# SH5_-_ARM_CONTROLS.net
KiCad netlist of a schematic drawn in Altium Designer
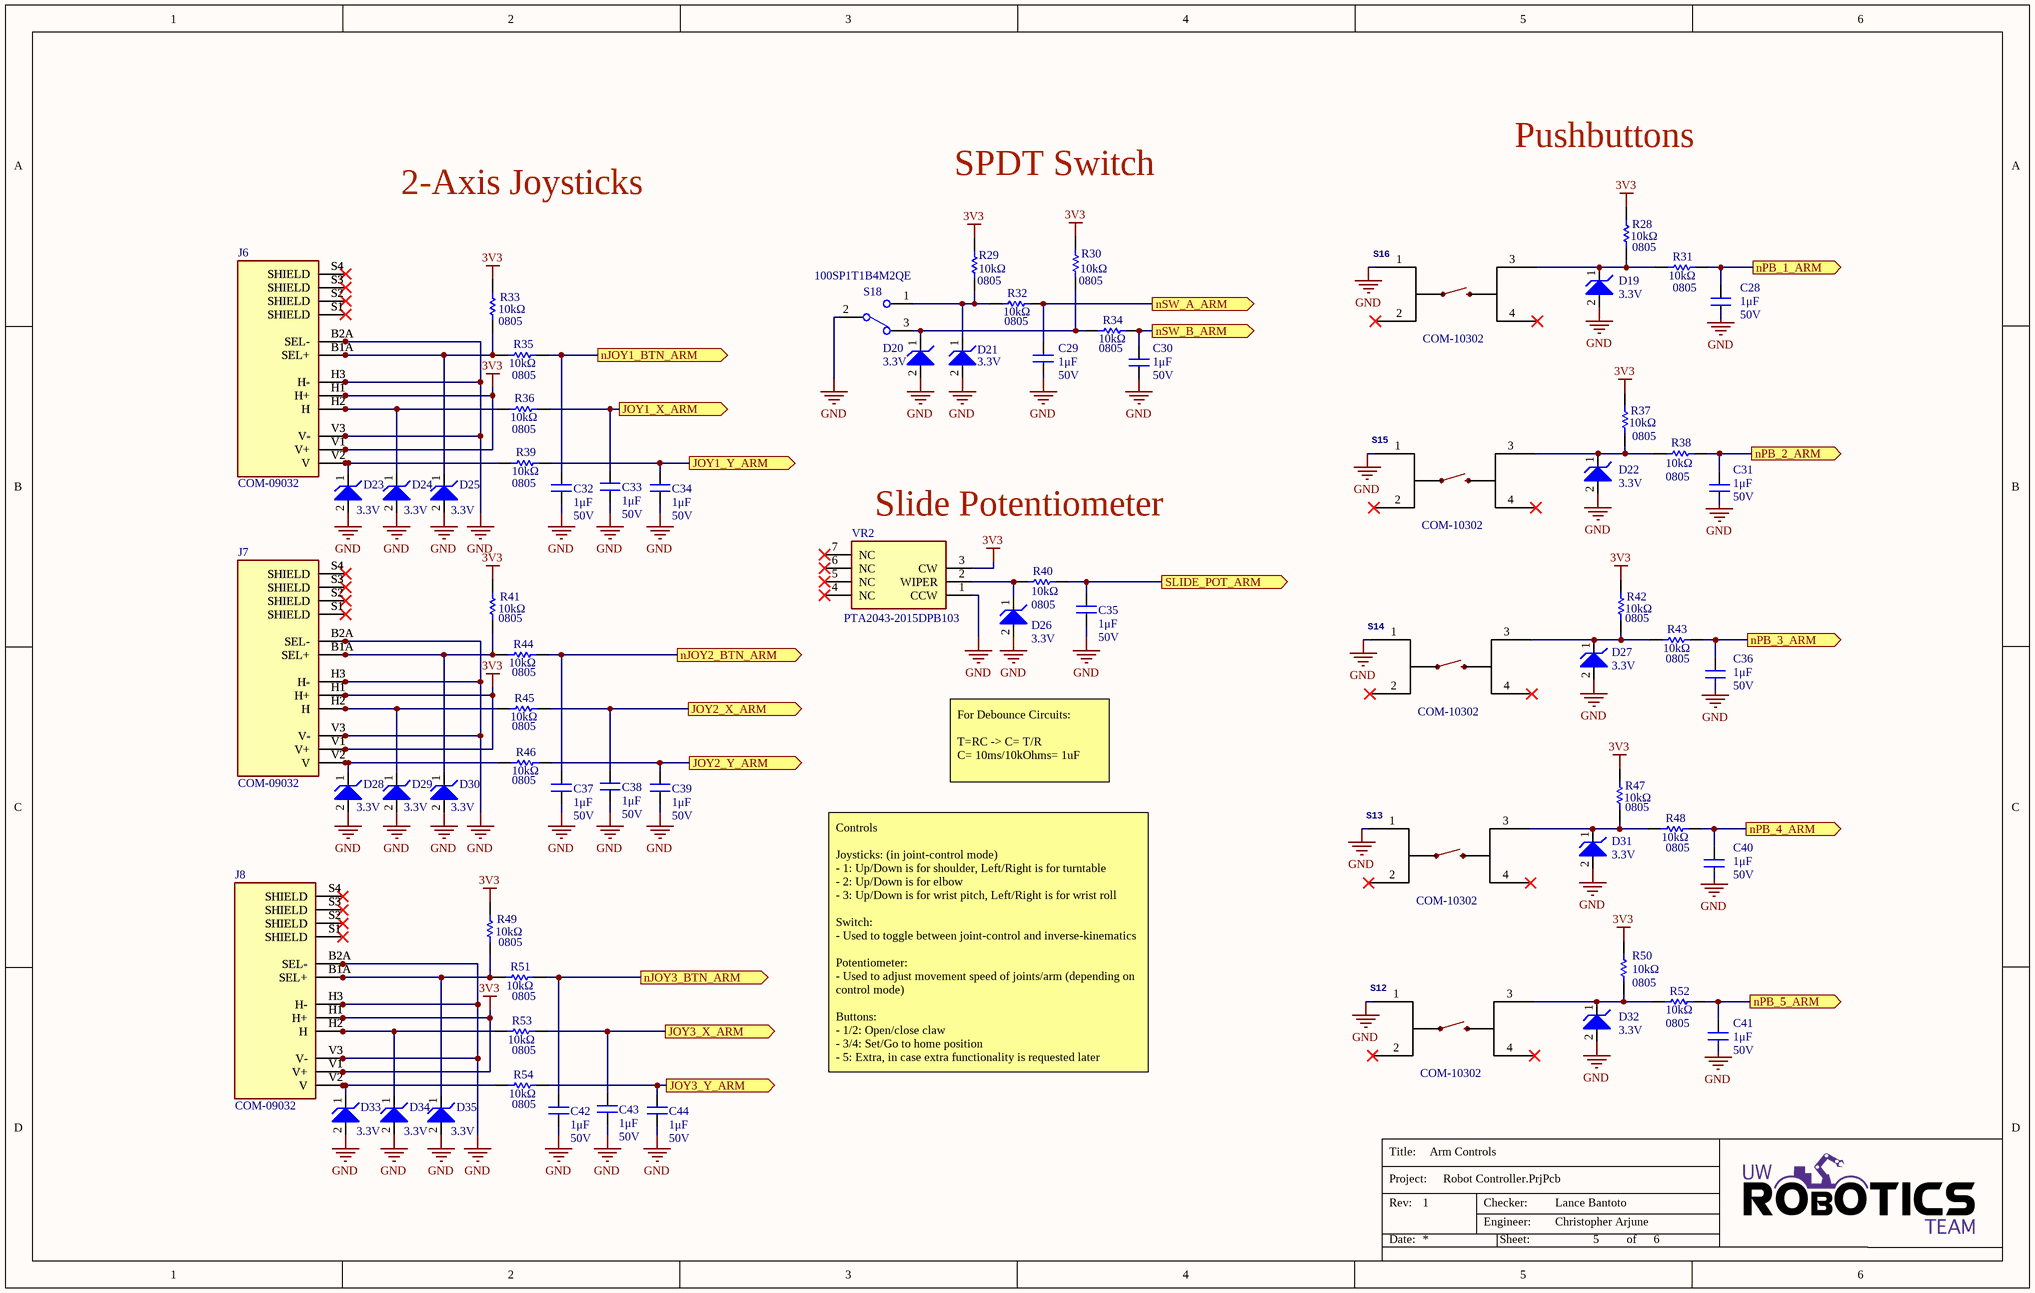
[diagram p0: SH5 - ARM CONTROLS.SchDoc]

(export (version "E")
  (design (tool "Eeschema 10.0.6"))
  (components
    (comp (ref "C28")
      (value "1μF")
      (footprint "CAP2012")
      (description "CAP CER 1UF 50V X7R 0805")
      (fields
        (field (name "VOLTAGE RATING") "50V")
        (field (name "LCSC PART #") "C28323")
        (field (name "Comment") "CAP_1uF_50V_0805")
      )
      (libsource (lib "UWRT_Schematic_Library_2020") (part "CAP_1uF_50V_0805"))
    )
    (comp (ref "C29")
      (value "1μF")
      (footprint "CAP2012")
      (description "CAP CER 1UF 50V X7R 0805")
      (fields
        (field (name "VOLTAGE RATING") "50V")
        (field (name "LCSC PART #") "C28323")
        (field (name "Comment") "CAP_1uF_50V_0805")
      )
      (libsource (lib "UWRT_Schematic_Library_2020") (part "CAP_1uF_50V_0805"))
    )
    (comp (ref "C30")
      (value "1μF")
      (footprint "CAP2012")
      (description "CAP CER 1UF 50V X7R 0805")
      (fields
        (field (name "VOLTAGE RATING") "50V")
        (field (name "LCSC PART #") "C28323")
        (field (name "Comment") "CAP_1uF_50V_0805")
      )
      (libsource (lib "UWRT_Schematic_Library_2020") (part "CAP_1uF_50V_0805"))
    )
    (comp (ref "C31")
      (value "1μF")
      (footprint "CAP2012")
      (description "CAP CER 1UF 50V X7R 0805")
      (fields
        (field (name "VOLTAGE RATING") "50V")
        (field (name "LCSC PART #") "C28323")
        (field (name "Comment") "CAP_1uF_50V_0805")
      )
      (libsource (lib "UWRT_Schematic_Library_2020") (part "CAP_1uF_50V_0805"))
    )
    (comp (ref "C32")
      (value "1μF")
      (footprint "CAP2012")
      (description "CAP CER 1UF 50V X7R 0805")
      (fields
        (field (name "VOLTAGE RATING") "50V")
        (field (name "LCSC PART #") "C28323")
        (field (name "Comment") "CAP_1uF_50V_0805")
      )
      (libsource (lib "UWRT_Schematic_Library_2020") (part "CAP_1uF_50V_0805"))
    )
    (comp (ref "C33")
      (value "1μF")
      (footprint "CAP2012")
      (description "CAP CER 1UF 50V X7R 0805")
      (fields
        (field (name "VOLTAGE RATING") "50V")
        (field (name "LCSC PART #") "C28323")
        (field (name "Comment") "CAP_1uF_50V_0805")
      )
      (libsource (lib "UWRT_Schematic_Library_2020") (part "CAP_1uF_50V_0805"))
    )
    (comp (ref "C34")
      (value "1μF")
      (footprint "CAP2012")
      (description "CAP CER 1UF 50V X7R 0805")
      (fields
        (field (name "VOLTAGE RATING") "50V")
        (field (name "LCSC PART #") "C28323")
        (field (name "Comment") "CAP_1uF_50V_0805")
      )
      (libsource (lib "UWRT_Schematic_Library_2020") (part "CAP_1uF_50V_0805"))
    )
    (comp (ref "C35")
      (value "1μF")
      (footprint "CAP2012")
      (description "CAP CER 1UF 50V X7R 0805")
      (fields
        (field (name "VOLTAGE RATING") "50V")
        (field (name "LCSC PART #") "C28323")
        (field (name "Comment") "CAP_1uF_50V_0805")
      )
      (libsource (lib "UWRT_Schematic_Library_2020") (part "CAP_1uF_50V_0805"))
    )
    (comp (ref "C36")
      (value "1μF")
      (footprint "CAP2012")
      (description "CAP CER 1UF 50V X7R 0805")
      (fields
        (field (name "VOLTAGE RATING") "50V")
        (field (name "LCSC PART #") "C28323")
        (field (name "Comment") "CAP_1uF_50V_0805")
      )
      (libsource (lib "UWRT_Schematic_Library_2020") (part "CAP_1uF_50V_0805"))
    )
    (comp (ref "C37")
      (value "1μF")
      (footprint "CAP2012")
      (description "CAP CER 1UF 50V X7R 0805")
      (fields
        (field (name "VOLTAGE RATING") "50V")
        (field (name "LCSC PART #") "C28323")
        (field (name "Comment") "CAP_1uF_50V_0805")
      )
      (libsource (lib "UWRT_Schematic_Library_2020") (part "CAP_1uF_50V_0805"))
    )
    (comp (ref "C38")
      (value "1μF")
      (footprint "CAP2012")
      (description "CAP CER 1UF 50V X7R 0805")
      (fields
        (field (name "VOLTAGE RATING") "50V")
        (field (name "LCSC PART #") "C28323")
        (field (name "Comment") "CAP_1uF_50V_0805")
      )
      (libsource (lib "UWRT_Schematic_Library_2020") (part "CAP_1uF_50V_0805"))
    )
    (comp (ref "C39")
      (value "1μF")
      (footprint "CAP2012")
      (description "CAP CER 1UF 50V X7R 0805")
      (fields
        (field (name "VOLTAGE RATING") "50V")
        (field (name "LCSC PART #") "C28323")
        (field (name "Comment") "CAP_1uF_50V_0805")
      )
      (libsource (lib "UWRT_Schematic_Library_2020") (part "CAP_1uF_50V_0805"))
    )
    (comp (ref "C40")
      (value "1μF")
      (footprint "CAP2012")
      (description "CAP CER 1UF 50V X7R 0805")
      (fields
        (field (name "VOLTAGE RATING") "50V")
        (field (name "LCSC PART #") "C28323")
        (field (name "Comment") "CAP_1uF_50V_0805")
      )
      (libsource (lib "UWRT_Schematic_Library_2020") (part "CAP_1uF_50V_0805"))
    )
    (comp (ref "C41")
      (value "1μF")
      (footprint "CAP2012")
      (description "CAP CER 1UF 50V X7R 0805")
      (fields
        (field (name "VOLTAGE RATING") "50V")
        (field (name "LCSC PART #") "C28323")
        (field (name "Comment") "CAP_1uF_50V_0805")
      )
      (libsource (lib "UWRT_Schematic_Library_2020") (part "CAP_1uF_50V_0805"))
    )
    (comp (ref "C42")
      (value "1μF")
      (footprint "CAP2012")
      (description "CAP CER 1UF 50V X7R 0805")
      (fields
        (field (name "VOLTAGE RATING") "50V")
        (field (name "LCSC PART #") "C28323")
        (field (name "Comment") "CAP_1uF_50V_0805")
      )
      (libsource (lib "UWRT_Schematic_Library_2020") (part "CAP_1uF_50V_0805"))
    )
    (comp (ref "C43")
      (value "1μF")
      (footprint "CAP2012")
      (description "CAP CER 1UF 50V X7R 0805")
      (fields
        (field (name "VOLTAGE RATING") "50V")
        (field (name "LCSC PART #") "C28323")
        (field (name "Comment") "CAP_1uF_50V_0805")
      )
      (libsource (lib "UWRT_Schematic_Library_2020") (part "CAP_1uF_50V_0805"))
    )
    (comp (ref "C44")
      (value "1μF")
      (footprint "CAP2012")
      (description "CAP CER 1UF 50V X7R 0805")
      (fields
        (field (name "VOLTAGE RATING") "50V")
        (field (name "LCSC PART #") "C28323")
        (field (name "Comment") "CAP_1uF_50V_0805")
      )
      (libsource (lib "UWRT_Schematic_Library_2020") (part "CAP_1uF_50V_0805"))
    )
    (comp (ref "D19")
      (value "TVS_DIODE_UNIDIR_3.3V")
      (description "TVS DIODE 3.3V 14.1V SOD523")
      (fields (field (name "LCSC PART #") "C61148") (field (name "VOLTAGE - REVERSE STANDOFF (TYP)") "3.3V"))
      (libsource (lib "UWRT_Schematic_Library_2020") (part "TVS_DIODE_UNIDIR_3.3V"))
    )
    (comp (ref "D20")
      (value "TVS_DIODE_UNIDIR_3.3V")
      (description "TVS DIODE 3.3V 14.1V SOD523")
      (fields (field (name "LCSC PART #") "C61148") (field (name "VOLTAGE - REVERSE STANDOFF (TYP)") "3.3V"))
      (libsource (lib "UWRT_Schematic_Library_2020") (part "TVS_DIODE_UNIDIR_3.3V"))
    )
    (comp (ref "D21")
      (value "TVS_DIODE_UNIDIR_3.3V")
      (description "TVS DIODE 3.3V 14.1V SOD523")
      (fields (field (name "LCSC PART #") "C61148") (field (name "VOLTAGE - REVERSE STANDOFF (TYP)") "3.3V"))
      (libsource (lib "UWRT_Schematic_Library_2020") (part "TVS_DIODE_UNIDIR_3.3V"))
    )
    (comp (ref "D22")
      (value "TVS_DIODE_UNIDIR_3.3V")
      (description "TVS DIODE 3.3V 14.1V SOD523")
      (fields (field (name "LCSC PART #") "C61148") (field (name "VOLTAGE - REVERSE STANDOFF (TYP)") "3.3V"))
      (libsource (lib "UWRT_Schematic_Library_2020") (part "TVS_DIODE_UNIDIR_3.3V"))
    )
    (comp (ref "D23")
      (value "TVS_DIODE_UNIDIR_3.3V")
      (description "TVS DIODE 3.3V 14.1V SOD523")
      (fields (field (name "LCSC PART #") "C61148") (field (name "VOLTAGE - REVERSE STANDOFF (TYP)") "3.3V"))
      (libsource (lib "UWRT_Schematic_Library_2020") (part "TVS_DIODE_UNIDIR_3.3V"))
    )
    (comp (ref "D24")
      (value "TVS_DIODE_UNIDIR_3.3V")
      (description "TVS DIODE 3.3V 14.1V SOD523")
      (fields (field (name "LCSC PART #") "C61148") (field (name "VOLTAGE - REVERSE STANDOFF (TYP)") "3.3V"))
      (libsource (lib "UWRT_Schematic_Library_2020") (part "TVS_DIODE_UNIDIR_3.3V"))
    )
    (comp (ref "D25")
      (value "TVS_DIODE_UNIDIR_3.3V")
      (description "TVS DIODE 3.3V 14.1V SOD523")
      (fields (field (name "LCSC PART #") "C61148") (field (name "VOLTAGE - REVERSE STANDOFF (TYP)") "3.3V"))
      (libsource (lib "UWRT_Schematic_Library_2020") (part "TVS_DIODE_UNIDIR_3.3V"))
    )
    (comp (ref "D26")
      (value "TVS_DIODE_UNIDIR_3.3V")
      (description "TVS DIODE 3.3V 14.1V SOD523")
      (fields (field (name "LCSC PART #") "C61148") (field (name "VOLTAGE - REVERSE STANDOFF (TYP)") "3.3V"))
      (libsource (lib "UWRT_Schematic_Library_2020") (part "TVS_DIODE_UNIDIR_3.3V"))
    )
    (comp (ref "D27")
      (value "TVS_DIODE_UNIDIR_3.3V")
      (description "TVS DIODE 3.3V 14.1V SOD523")
      (fields (field (name "LCSC PART #") "C61148") (field (name "VOLTAGE - REVERSE STANDOFF (TYP)") "3.3V"))
      (libsource (lib "UWRT_Schematic_Library_2020") (part "TVS_DIODE_UNIDIR_3.3V"))
    )
    (comp (ref "D28")
      (value "TVS_DIODE_UNIDIR_3.3V")
      (description "TVS DIODE 3.3V 14.1V SOD523")
      (fields (field (name "LCSC PART #") "C61148") (field (name "VOLTAGE - REVERSE STANDOFF (TYP)") "3.3V"))
      (libsource (lib "UWRT_Schematic_Library_2020") (part "TVS_DIODE_UNIDIR_3.3V"))
    )
    (comp (ref "D29")
      (value "TVS_DIODE_UNIDIR_3.3V")
      (description "TVS DIODE 3.3V 14.1V SOD523")
      (fields (field (name "LCSC PART #") "C61148") (field (name "VOLTAGE - REVERSE STANDOFF (TYP)") "3.3V"))
      (libsource (lib "UWRT_Schematic_Library_2020") (part "TVS_DIODE_UNIDIR_3.3V"))
    )
    (comp (ref "D30")
      (value "TVS_DIODE_UNIDIR_3.3V")
      (description "TVS DIODE 3.3V 14.1V SOD523")
      (fields (field (name "LCSC PART #") "C61148") (field (name "VOLTAGE - REVERSE STANDOFF (TYP)") "3.3V"))
      (libsource (lib "UWRT_Schematic_Library_2020") (part "TVS_DIODE_UNIDIR_3.3V"))
    )
    (comp (ref "D31")
      (value "TVS_DIODE_UNIDIR_3.3V")
      (description "TVS DIODE 3.3V 14.1V SOD523")
      (fields (field (name "LCSC PART #") "C61148") (field (name "VOLTAGE - REVERSE STANDOFF (TYP)") "3.3V"))
      (libsource (lib "UWRT_Schematic_Library_2020") (part "TVS_DIODE_UNIDIR_3.3V"))
    )
    (comp (ref "D32")
      (value "TVS_DIODE_UNIDIR_3.3V")
      (description "TVS DIODE 3.3V 14.1V SOD523")
      (fields (field (name "LCSC PART #") "C61148") (field (name "VOLTAGE - REVERSE STANDOFF (TYP)") "3.3V"))
      (libsource (lib "UWRT_Schematic_Library_2020") (part "TVS_DIODE_UNIDIR_3.3V"))
    )
    (comp (ref "D33")
      (value "TVS_DIODE_UNIDIR_3.3V")
      (description "TVS DIODE 3.3V 14.1V SOD523")
      (fields (field (name "LCSC PART #") "C61148") (field (name "VOLTAGE - REVERSE STANDOFF (TYP)") "3.3V"))
      (libsource (lib "UWRT_Schematic_Library_2020") (part "TVS_DIODE_UNIDIR_3.3V"))
    )
    (comp (ref "D34")
      (value "TVS_DIODE_UNIDIR_3.3V")
      (description "TVS DIODE 3.3V 14.1V SOD523")
      (fields (field (name "LCSC PART #") "C61148") (field (name "VOLTAGE - REVERSE STANDOFF (TYP)") "3.3V"))
      (libsource (lib "UWRT_Schematic_Library_2020") (part "TVS_DIODE_UNIDIR_3.3V"))
    )
    (comp (ref "D35")
      (value "TVS_DIODE_UNIDIR_3.3V")
      (description "TVS DIODE 3.3V 14.1V SOD523")
      (fields (field (name "LCSC PART #") "C61148") (field (name "VOLTAGE - REVERSE STANDOFF (TYP)") "3.3V"))
      (libsource (lib "UWRT_Schematic_Library_2020") (part "TVS_DIODE_UNIDIR_3.3V"))
    )
    (comp (ref "J6")
      (value "2_AXIS_JOYSTICK")
      (footprint "2_AXIS_JOYSTICK")
      (description "JOYSTICK 10K OHM 2 AXIS TH")
      (fields (field (name "MANUFACTURER PART NUMBER 1") "COM-09032"))
      (libsource (lib "UWRT_Schematic_Library_2020") (part "2_AXIS_JOYSTICK"))
    )
    (comp (ref "J7")
      (value "2_AXIS_JOYSTICK")
      (footprint "2_AXIS_JOYSTICK")
      (description "JOYSTICK 10K OHM 2 AXIS TH")
      (fields (field (name "MANUFACTURER PART NUMBER 1") "COM-09032"))
      (libsource (lib "UWRT_Schematic_Library_2020") (part "2_AXIS_JOYSTICK"))
    )
    (comp (ref "J8")
      (value "2_AXIS_JOYSTICK")
      (footprint "2_AXIS_JOYSTICK")
      (description "JOYSTICK 10K OHM 2 AXIS TH")
      (fields (field (name "MANUFACTURER PART NUMBER 1") "COM-09032"))
      (libsource (lib "UWRT_Schematic_Library_2020") (part "2_AXIS_JOYSTICK"))
    )
    (comp (ref "R28")
      (value "10kΩ")
      (footprint "RESC0805")
      (description "RES 10K OHM 5% 1/8W 0805")
      (fields
        (field (name "LCSC PART #") "C17414")
        (field (name "PACKAGE/FOOTPRINT") "0805")
        (field (name "Comment") "RES_10kΩ_0805_5%")
      )
      (libsource (lib "UWRT_Schematic_Library_2020") (part "RES_10kΩ_0805_5%"))
    )
    (comp (ref "R29")
      (value "10kΩ")
      (footprint "RESC0805")
      (description "RES 10K OHM 5% 1/8W 0805")
      (fields
        (field (name "LCSC PART #") "C17414")
        (field (name "PACKAGE/FOOTPRINT") "0805")
        (field (name "Comment") "RES_10kΩ_0805_5%")
      )
      (libsource (lib "UWRT_Schematic_Library_2020") (part "RES_10kΩ_0805_5%"))
    )
    (comp (ref "R30")
      (value "10kΩ")
      (footprint "RESC0805")
      (description "RES 10K OHM 5% 1/8W 0805")
      (fields
        (field (name "LCSC PART #") "C17414")
        (field (name "PACKAGE/FOOTPRINT") "0805")
        (field (name "Comment") "RES_10kΩ_0805_5%")
      )
      (libsource (lib "UWRT_Schematic_Library_2020") (part "RES_10kΩ_0805_5%"))
    )
    (comp (ref "R31")
      (value "10kΩ")
      (footprint "RESC0805")
      (description "RES 10K OHM 5% 1/8W 0805")
      (fields
        (field (name "LCSC PART #") "C17414")
        (field (name "PACKAGE/FOOTPRINT") "0805")
        (field (name "Comment") "RES_10kΩ_0805_5%")
      )
      (libsource (lib "UWRT_Schematic_Library_2020") (part "RES_10kΩ_0805_5%"))
    )
    (comp (ref "R32")
      (value "10kΩ")
      (footprint "RESC0805")
      (description "RES 10K OHM 5% 1/8W 0805")
      (fields
        (field (name "LCSC PART #") "C17414")
        (field (name "PACKAGE/FOOTPRINT") "0805")
        (field (name "Comment") "RES_10kΩ_0805_5%")
      )
      (libsource (lib "UWRT_Schematic_Library_2020") (part "RES_10kΩ_0805_5%"))
    )
    (comp (ref "R33")
      (value "10kΩ")
      (footprint "RESC0805")
      (description "RES 10K OHM 5% 1/8W 0805")
      (fields
        (field (name "LCSC PART #") "C17414")
        (field (name "PACKAGE/FOOTPRINT") "0805")
        (field (name "Comment") "RES_10kΩ_0805_5%")
      )
      (libsource (lib "UWRT_Schematic_Library_2020") (part "RES_10kΩ_0805_5%"))
    )
    (comp (ref "R34")
      (value "10kΩ")
      (footprint "RESC0805")
      (description "RES 10K OHM 5% 1/8W 0805")
      (fields
        (field (name "LCSC PART #") "C17414")
        (field (name "PACKAGE/FOOTPRINT") "0805")
        (field (name "Comment") "RES_10kΩ_0805_5%")
      )
      (libsource (lib "UWRT_Schematic_Library_2020") (part "RES_10kΩ_0805_5%"))
    )
    (comp (ref "R35")
      (value "10kΩ")
      (footprint "RESC0805")
      (description "RES 10K OHM 5% 1/8W 0805")
      (fields
        (field (name "LCSC PART #") "C17414")
        (field (name "PACKAGE/FOOTPRINT") "0805")
        (field (name "Comment") "RES_10kΩ_0805_5%")
      )
      (libsource (lib "UWRT_Schematic_Library_2020") (part "RES_10kΩ_0805_5%"))
    )
    (comp (ref "R36")
      (value "10kΩ")
      (footprint "RESC0805")
      (description "RES 10K OHM 5% 1/8W 0805")
      (fields
        (field (name "LCSC PART #") "C17414")
        (field (name "PACKAGE/FOOTPRINT") "0805")
        (field (name "Comment") "RES_10kΩ_0805_5%")
      )
      (libsource (lib "UWRT_Schematic_Library_2020") (part "RES_10kΩ_0805_5%"))
    )
    (comp (ref "R37")
      (value "10kΩ")
      (footprint "RESC0805")
      (description "RES 10K OHM 5% 1/8W 0805")
      (fields
        (field (name "LCSC PART #") "C17414")
        (field (name "PACKAGE/FOOTPRINT") "0805")
        (field (name "Comment") "RES_10kΩ_0805_5%")
      )
      (libsource (lib "UWRT_Schematic_Library_2020") (part "RES_10kΩ_0805_5%"))
    )
    (comp (ref "R38")
      (value "10kΩ")
      (footprint "RESC0805")
      (description "RES 10K OHM 5% 1/8W 0805")
      (fields
        (field (name "LCSC PART #") "C17414")
        (field (name "PACKAGE/FOOTPRINT") "0805")
        (field (name "Comment") "RES_10kΩ_0805_5%")
      )
      (libsource (lib "UWRT_Schematic_Library_2020") (part "RES_10kΩ_0805_5%"))
    )
    (comp (ref "R39")
      (value "10kΩ")
      (footprint "RESC0805")
      (description "RES 10K OHM 5% 1/8W 0805")
      (fields
        (field (name "LCSC PART #") "C17414")
        (field (name "PACKAGE/FOOTPRINT") "0805")
        (field (name "Comment") "RES_10kΩ_0805_5%")
      )
      (libsource (lib "UWRT_Schematic_Library_2020") (part "RES_10kΩ_0805_5%"))
    )
    (comp (ref "R40")
      (value "10kΩ")
      (footprint "RESC0805")
      (description "RES 10K OHM 5% 1/8W 0805")
      (fields
        (field (name "LCSC PART #") "C17414")
        (field (name "PACKAGE/FOOTPRINT") "0805")
        (field (name "Comment") "RES_10kΩ_0805_5%")
      )
      (libsource (lib "UWRT_Schematic_Library_2020") (part "RES_10kΩ_0805_5%"))
    )
    (comp (ref "R41")
      (value "10kΩ")
      (footprint "RESC0805")
      (description "RES 10K OHM 5% 1/8W 0805")
      (fields
        (field (name "LCSC PART #") "C17414")
        (field (name "PACKAGE/FOOTPRINT") "0805")
        (field (name "Comment") "RES_10kΩ_0805_5%")
      )
      (libsource (lib "UWRT_Schematic_Library_2020") (part "RES_10kΩ_0805_5%"))
    )
    (comp (ref "R42")
      (value "10kΩ")
      (footprint "RESC0805")
      (description "RES 10K OHM 5% 1/8W 0805")
      (fields
        (field (name "LCSC PART #") "C17414")
        (field (name "PACKAGE/FOOTPRINT") "0805")
        (field (name "Comment") "RES_10kΩ_0805_5%")
      )
      (libsource (lib "UWRT_Schematic_Library_2020") (part "RES_10kΩ_0805_5%"))
    )
    (comp (ref "R43")
      (value "10kΩ")
      (footprint "RESC0805")
      (description "RES 10K OHM 5% 1/8W 0805")
      (fields
        (field (name "LCSC PART #") "C17414")
        (field (name "PACKAGE/FOOTPRINT") "0805")
        (field (name "Comment") "RES_10kΩ_0805_5%")
      )
      (libsource (lib "UWRT_Schematic_Library_2020") (part "RES_10kΩ_0805_5%"))
    )
    (comp (ref "R44")
      (value "10kΩ")
      (footprint "RESC0805")
      (description "RES 10K OHM 5% 1/8W 0805")
      (fields
        (field (name "LCSC PART #") "C17414")
        (field (name "PACKAGE/FOOTPRINT") "0805")
        (field (name "Comment") "RES_10kΩ_0805_5%")
      )
      (libsource (lib "UWRT_Schematic_Library_2020") (part "RES_10kΩ_0805_5%"))
    )
    (comp (ref "R45")
      (value "10kΩ")
      (footprint "RESC0805")
      (description "RES 10K OHM 5% 1/8W 0805")
      (fields
        (field (name "LCSC PART #") "C17414")
        (field (name "PACKAGE/FOOTPRINT") "0805")
        (field (name "Comment") "RES_10kΩ_0805_5%")
      )
      (libsource (lib "UWRT_Schematic_Library_2020") (part "RES_10kΩ_0805_5%"))
    )
    (comp (ref "R46")
      (value "10kΩ")
      (footprint "RESC0805")
      (description "RES 10K OHM 5% 1/8W 0805")
      (fields
        (field (name "LCSC PART #") "C17414")
        (field (name "PACKAGE/FOOTPRINT") "0805")
        (field (name "Comment") "RES_10kΩ_0805_5%")
      )
      (libsource (lib "UWRT_Schematic_Library_2020") (part "RES_10kΩ_0805_5%"))
    )
    (comp (ref "R47")
      (value "10kΩ")
      (footprint "RESC0805")
      (description "RES 10K OHM 5% 1/8W 0805")
      (fields
        (field (name "LCSC PART #") "C17414")
        (field (name "PACKAGE/FOOTPRINT") "0805")
        (field (name "Comment") "RES_10kΩ_0805_5%")
      )
      (libsource (lib "UWRT_Schematic_Library_2020") (part "RES_10kΩ_0805_5%"))
    )
    (comp (ref "R48")
      (value "10kΩ")
      (footprint "RESC0805")
      (description "RES 10K OHM 5% 1/8W 0805")
      (fields
        (field (name "LCSC PART #") "C17414")
        (field (name "PACKAGE/FOOTPRINT") "0805")
        (field (name "Comment") "RES_10kΩ_0805_5%")
      )
      (libsource (lib "UWRT_Schematic_Library_2020") (part "RES_10kΩ_0805_5%"))
    )
    (comp (ref "R49")
      (value "10kΩ")
      (footprint "RESC0805")
      (description "RES 10K OHM 5% 1/8W 0805")
      (fields
        (field (name "LCSC PART #") "C17414")
        (field (name "PACKAGE/FOOTPRINT") "0805")
        (field (name "Comment") "RES_10kΩ_0805_5%")
      )
      (libsource (lib "UWRT_Schematic_Library_2020") (part "RES_10kΩ_0805_5%"))
    )
    (comp (ref "R50")
      (value "10kΩ")
      (footprint "RESC0805")
      (description "RES 10K OHM 5% 1/8W 0805")
      (fields
        (field (name "LCSC PART #") "C17414")
        (field (name "PACKAGE/FOOTPRINT") "0805")
        (field (name "Comment") "RES_10kΩ_0805_5%")
      )
      (libsource (lib "UWRT_Schematic_Library_2020") (part "RES_10kΩ_0805_5%"))
    )
    (comp (ref "R51")
      (value "10kΩ")
      (footprint "RESC0805")
      (description "RES 10K OHM 5% 1/8W 0805")
      (fields
        (field (name "LCSC PART #") "C17414")
        (field (name "PACKAGE/FOOTPRINT") "0805")
        (field (name "Comment") "RES_10kΩ_0805_5%")
      )
      (libsource (lib "UWRT_Schematic_Library_2020") (part "RES_10kΩ_0805_5%"))
    )
    (comp (ref "R52")
      (value "10kΩ")
      (footprint "RESC0805")
      (description "RES 10K OHM 5% 1/8W 0805")
      (fields
        (field (name "LCSC PART #") "C17414")
        (field (name "PACKAGE/FOOTPRINT") "0805")
        (field (name "Comment") "RES_10kΩ_0805_5%")
      )
      (libsource (lib "UWRT_Schematic_Library_2020") (part "RES_10kΩ_0805_5%"))
    )
    (comp (ref "R53")
      (value "10kΩ")
      (footprint "RESC0805")
      (description "RES 10K OHM 5% 1/8W 0805")
      (fields
        (field (name "LCSC PART #") "C17414")
        (field (name "PACKAGE/FOOTPRINT") "0805")
        (field (name "Comment") "RES_10kΩ_0805_5%")
      )
      (libsource (lib "UWRT_Schematic_Library_2020") (part "RES_10kΩ_0805_5%"))
    )
    (comp (ref "R54")
      (value "10kΩ")
      (footprint "RESC0805")
      (description "RES 10K OHM 5% 1/8W 0805")
      (fields
        (field (name "LCSC PART #") "C17414")
        (field (name "PACKAGE/FOOTPRINT") "0805")
        (field (name "Comment") "RES_10kΩ_0805_5%")
      )
      (libsource (lib "UWRT_Schematic_Library_2020") (part "RES_10kΩ_0805_5%"))
    )
    (comp (ref "S12")
      (value "SW_MOMENTARY_PUSHBUTTON")
      (footprint "TACTILE_SWITCH_PTH_12MM")
      (description "TACTILE MOMENTARY PUSHBUTTON SPST")
      (fields (field (name "MANUFACTURER PART NUMBER 1") "COM-10302"))
      (libsource (lib "UWRT_Schematic_Library_2020") (part "SW_MOMENTARY_PUSHBUTTON"))
    )
    (comp (ref "S13")
      (value "SW_MOMENTARY_PUSHBUTTON")
      (footprint "TACTILE_SWITCH_PTH_12MM")
      (description "TACTILE MOMENTARY PUSHBUTTON SPST")
      (fields (field (name "MANUFACTURER PART NUMBER 1") "COM-10302"))
      (libsource (lib "UWRT_Schematic_Library_2020") (part "SW_MOMENTARY_PUSHBUTTON"))
    )
    (comp (ref "S14")
      (value "SW_MOMENTARY_PUSHBUTTON")
      (footprint "TACTILE_SWITCH_PTH_12MM")
      (description "TACTILE MOMENTARY PUSHBUTTON SPST")
      (fields (field (name "MANUFACTURER PART NUMBER 1") "COM-10302"))
      (libsource (lib "UWRT_Schematic_Library_2020") (part "SW_MOMENTARY_PUSHBUTTON"))
    )
    (comp (ref "S15")
      (value "SW_MOMENTARY_PUSHBUTTON")
      (footprint "TACTILE_SWITCH_PTH_12MM")
      (description "TACTILE MOMENTARY PUSHBUTTON SPST")
      (fields (field (name "MANUFACTURER PART NUMBER 1") "COM-10302"))
      (libsource (lib "UWRT_Schematic_Library_2020") (part "SW_MOMENTARY_PUSHBUTTON"))
    )
    (comp (ref "S16")
      (value "SW_MOMENTARY_PUSHBUTTON")
      (footprint "TACTILE_SWITCH_PTH_12MM")
      (description "TACTILE MOMENTARY PUSHBUTTON SPST")
      (fields (field (name "MANUFACTURER PART NUMBER 1") "COM-10302"))
      (libsource (lib "UWRT_Schematic_Library_2020") (part "SW_MOMENTARY_PUSHBUTTON"))
    )
    (comp (ref "S18")
      (value "100SP1T1B4M2QE")
      (footprint "100SP1T1B4M2QE")
      (description "SWITCH TOGGLE SPDT 5A 120V")
      (fields (field (name "MANUFACTURER PART NUMBER 1") "100SP1T1B4M2QE"))
      (libsource (lib "UWRT_Schematic_Library_2020") (part "SW_SPDT"))
    )
    (comp (ref "VR2")
      (value "POT_10K_SLIDE")
      (footprint "PTA20432015CPB103")
      (description "SLIDE POT 10K OHM 0.1W TOP 20MM")
      (fields (field (name "MANUFACTURER PART NUMBER 1") "PTA2043-2015DPB103"))
      (libsource (lib "UWRT_Schematic_Library_2020") (part "POT_10K_SLIDE"))
    )
  )
  (nets
    (net (code "1") (name "/JOY1_X_ARM") (class "Default")
      (node (ref "C33") (pin "2") (pinfunction "2_2") (pintype "passive"))
      (node (ref "R36") (pin "2") (pinfunction "2_2") (pintype "passive"))
    )
    (net (code "2") (name "/JOY1_Y_ARM") (class "Default")
      (node (ref "C34") (pin "2") (pinfunction "2_2") (pintype "passive"))
      (node (ref "R39") (pin "2") (pinfunction "2_2") (pintype "passive"))
    )
    (net (code "3") (name "/JOY2_X_ARM") (class "Default")
      (node (ref "C38") (pin "2") (pinfunction "2_2") (pintype "passive"))
      (node (ref "R45") (pin "2") (pinfunction "2_2") (pintype "passive"))
    )
    (net (code "4") (name "/JOY2_Y_ARM") (class "Default")
      (node (ref "C39") (pin "2") (pinfunction "2_2") (pintype "passive"))
      (node (ref "R46") (pin "2") (pinfunction "2_2") (pintype "passive"))
    )
    (net (code "5") (name "/JOY3_X_ARM") (class "Default")
      (node (ref "C43") (pin "2") (pinfunction "2_2") (pintype "passive"))
      (node (ref "R53") (pin "2") (pinfunction "2_2") (pintype "passive"))
    )
    (net (code "6") (name "/JOY3_Y_ARM") (class "Default")
      (node (ref "C44") (pin "2") (pinfunction "2_2") (pintype "passive"))
      (node (ref "R54") (pin "2") (pinfunction "2_2") (pintype "passive"))
    )
    (net (code "7") (name "/SLIDE_POT_ARM") (class "Default")
      (node (ref "C35") (pin "2") (pinfunction "2_2") (pintype "passive"))
      (node (ref "R40") (pin "2") (pinfunction "2_2") (pintype "passive"))
    )
    (net (code "8") (name "/nJOY1_BTN_ARM") (class "Default")
      (node (ref "C32") (pin "2") (pinfunction "2_2") (pintype "passive"))
      (node (ref "R35") (pin "2") (pinfunction "2_2") (pintype "passive"))
    )
    (net (code "9") (name "/nJOY2_BTN_ARM") (class "Default")
      (node (ref "C37") (pin "2") (pinfunction "2_2") (pintype "passive"))
      (node (ref "R44") (pin "2") (pinfunction "2_2") (pintype "passive"))
    )
    (net (code "10") (name "/nJOY3_BTN_ARM") (class "Default")
      (node (ref "C42") (pin "2") (pinfunction "2_2") (pintype "passive"))
      (node (ref "R51") (pin "2") (pinfunction "2_2") (pintype "passive"))
    )
    (net (code "11") (name "/nPB_1_ARM") (class "Default")
      (node (ref "C28") (pin "2") (pinfunction "2_2") (pintype "passive"))
      (node (ref "R31") (pin "2") (pinfunction "2_2") (pintype "passive"))
    )
    (net (code "12") (name "/nPB_2_ARM") (class "Default")
      (node (ref "C31") (pin "2") (pinfunction "2_2") (pintype "passive"))
      (node (ref "R38") (pin "2") (pinfunction "2_2") (pintype "passive"))
    )
    (net (code "13") (name "/nPB_3_ARM") (class "Default")
      (node (ref "C36") (pin "2") (pinfunction "2_2") (pintype "passive"))
      (node (ref "R43") (pin "2") (pinfunction "2_2") (pintype "passive"))
    )
    (net (code "14") (name "/nPB_4_ARM") (class "Default")
      (node (ref "C40") (pin "2") (pinfunction "2_2") (pintype "passive"))
      (node (ref "R48") (pin "2") (pinfunction "2_2") (pintype "passive"))
    )
    (net (code "15") (name "/nPB_5_ARM") (class "Default")
      (node (ref "C41") (pin "2") (pinfunction "2_2") (pintype "passive"))
      (node (ref "R52") (pin "2") (pinfunction "2_2") (pintype "passive"))
    )
    (net (code "16") (name "/nSW_A_ARM") (class "Default")
      (node (ref "C29") (pin "2") (pinfunction "2_2") (pintype "passive"))
      (node (ref "R32") (pin "2") (pinfunction "2_2") (pintype "passive"))
    )
    (net (code "17") (name "/nSW_B_ARM") (class "Default")
      (node (ref "C30") (pin "2") (pinfunction "2_2") (pintype "passive"))
      (node (ref "R34") (pin "2") (pinfunction "2_2") (pintype "passive"))
    )
    (net (code "18") (name "3V3") (class "Default")
      (node (ref "J6") (pin "H1") (pinfunction "H+_H1") (pintype "passive"))
      (node (ref "J6") (pin "V1") (pinfunction "V+_V1") (pintype "passive"))
      (node (ref "J7") (pin "H1") (pinfunction "H+_H1") (pintype "passive"))
      (node (ref "J7") (pin "V1") (pinfunction "V+_V1") (pintype "passive"))
      (node (ref "J8") (pin "H1") (pinfunction "H+_H1") (pintype "passive"))
      (node (ref "J8") (pin "V1") (pinfunction "V+_V1") (pintype "passive"))
      (node (ref "R28") (pin "1") (pinfunction "1_1") (pintype "passive"))
      (node (ref "R29") (pin "1") (pinfunction "1_1") (pintype "passive"))
      (node (ref "R30") (pin "1") (pinfunction "1_1") (pintype "passive"))
      (node (ref "R33") (pin "1") (pinfunction "1_1") (pintype "passive"))
      (node (ref "R37") (pin "1") (pinfunction "1_1") (pintype "passive"))
      (node (ref "R41") (pin "1") (pinfunction "1_1") (pintype "passive"))
      (node (ref "R42") (pin "1") (pinfunction "1_1") (pintype "passive"))
      (node (ref "R47") (pin "1") (pinfunction "1_1") (pintype "passive"))
      (node (ref "R49") (pin "1") (pinfunction "1_1") (pintype "passive"))
      (node (ref "R50") (pin "1") (pinfunction "1_1") (pintype "passive"))
      (node (ref "VR2") (pin "3") (pinfunction "CW_3") (pintype "passive"))
    )
    (net (code "19") (name "GND") (class "Default")
      (node (ref "C28") (pin "1") (pinfunction "1_1") (pintype "passive"))
      (node (ref "C29") (pin "1") (pinfunction "1_1") (pintype "passive"))
      (node (ref "C30") (pin "1") (pinfunction "1_1") (pintype "passive"))
      (node (ref "C31") (pin "1") (pinfunction "1_1") (pintype "passive"))
      (node (ref "C32") (pin "1") (pinfunction "1_1") (pintype "passive"))
      (node (ref "C33") (pin "1") (pinfunction "1_1") (pintype "passive"))
      (node (ref "C34") (pin "1") (pinfunction "1_1") (pintype "passive"))
      (node (ref "C35") (pin "1") (pinfunction "1_1") (pintype "passive"))
      (node (ref "C36") (pin "1") (pinfunction "1_1") (pintype "passive"))
      (node (ref "C37") (pin "1") (pinfunction "1_1") (pintype "passive"))
      (node (ref "C38") (pin "1") (pinfunction "1_1") (pintype "passive"))
      (node (ref "C39") (pin "1") (pinfunction "1_1") (pintype "passive"))
      (node (ref "C40") (pin "1") (pinfunction "1_1") (pintype "passive"))
      (node (ref "C41") (pin "1") (pinfunction "1_1") (pintype "passive"))
      (node (ref "C42") (pin "1") (pinfunction "1_1") (pintype "passive"))
      (node (ref "C43") (pin "1") (pinfunction "1_1") (pintype "passive"))
      (node (ref "C44") (pin "1") (pinfunction "1_1") (pintype "passive"))
      (node (ref "D19") (pin "2") (pinfunction "2_2") (pintype "passive"))
      (node (ref "D20") (pin "2") (pinfunction "2_2") (pintype "passive"))
      (node (ref "D21") (pin "2") (pinfunction "2_2") (pintype "passive"))
      (node (ref "D22") (pin "2") (pinfunction "2_2") (pintype "passive"))
      (node (ref "D23") (pin "2") (pinfunction "2_2") (pintype "passive"))
      (node (ref "D24") (pin "2") (pinfunction "2_2") (pintype "passive"))
      (node (ref "D25") (pin "2") (pinfunction "2_2") (pintype "passive"))
      (node (ref "D26") (pin "2") (pinfunction "2_2") (pintype "passive"))
      (node (ref "D27") (pin "2") (pinfunction "2_2") (pintype "passive"))
      (node (ref "D28") (pin "2") (pinfunction "2_2") (pintype "passive"))
      (node (ref "D29") (pin "2") (pinfunction "2_2") (pintype "passive"))
      (node (ref "D30") (pin "2") (pinfunction "2_2") (pintype "passive"))
      (node (ref "D31") (pin "2") (pinfunction "2_2") (pintype "passive"))
      (node (ref "D32") (pin "2") (pinfunction "2_2") (pintype "passive"))
      (node (ref "D33") (pin "2") (pinfunction "2_2") (pintype "passive"))
      (node (ref "D34") (pin "2") (pinfunction "2_2") (pintype "passive"))
      (node (ref "D35") (pin "2") (pinfunction "2_2") (pintype "passive"))
      (node (ref "J6") (pin "B2A") (pinfunction "SEL-_B2A") (pintype "passive"))
      (node (ref "J6") (pin "H3") (pinfunction "H-_H3") (pintype "passive"))
      (node (ref "J6") (pin "V3") (pinfunction "V-_V3") (pintype "passive"))
      (node (ref "J7") (pin "B2A") (pinfunction "SEL-_B2A") (pintype "passive"))
      (node (ref "J7") (pin "H3") (pinfunction "H-_H3") (pintype "passive"))
      (node (ref "J7") (pin "V3") (pinfunction "V-_V3") (pintype "passive"))
      (node (ref "J8") (pin "B2A") (pinfunction "SEL-_B2A") (pintype "passive"))
      (node (ref "J8") (pin "H3") (pinfunction "H-_H3") (pintype "passive"))
      (node (ref "J8") (pin "V3") (pinfunction "V-_V3") (pintype "passive"))
      (node (ref "S12") (pin "1") (pinfunction "1_1") (pintype "passive"))
      (node (ref "S13") (pin "1") (pinfunction "1_1") (pintype "passive"))
      (node (ref "S14") (pin "1") (pinfunction "1_1") (pintype "passive"))
      (node (ref "S15") (pin "1") (pinfunction "1_1") (pintype "passive"))
      (node (ref "S16") (pin "1") (pinfunction "1_1") (pintype "passive"))
      (node (ref "S18") (pin "2") (pinfunction "2_2") (pintype "passive"))
      (node (ref "VR2") (pin "1") (pinfunction "CCW_1") (pintype "passive"))
    )
    (net (code "20") (name "Net-(D19-Pad1)") (class "Default")
      (node (ref "D19") (pin "1") (pinfunction "1_1") (pintype "passive"))
      (node (ref "R28") (pin "2") (pinfunction "2_2") (pintype "passive"))
      (node (ref "R31") (pin "1") (pinfunction "1_1") (pintype "passive"))
      (node (ref "S16") (pin "3") (pinfunction "3_3") (pintype "passive"))
    )
    (net (code "21") (name "Net-(D20-Pad1)") (class "Default")
      (node (ref "D20") (pin "1") (pinfunction "1_1") (pintype "passive"))
      (node (ref "R30") (pin "2") (pinfunction "2_2") (pintype "passive"))
      (node (ref "R34") (pin "1") (pinfunction "1_1") (pintype "passive"))
      (node (ref "S18") (pin "3") (pinfunction "3_3") (pintype "passive"))
    )
    (net (code "22") (name "Net-(D21-Pad1)") (class "Default")
      (node (ref "D21") (pin "1") (pinfunction "1_1") (pintype "passive"))
      (node (ref "R29") (pin "2") (pinfunction "2_2") (pintype "passive"))
      (node (ref "R32") (pin "1") (pinfunction "1_1") (pintype "passive"))
      (node (ref "S18") (pin "1") (pinfunction "1_1") (pintype "passive"))
    )
    (net (code "23") (name "Net-(D22-Pad1)") (class "Default")
      (node (ref "D22") (pin "1") (pinfunction "1_1") (pintype "passive"))
      (node (ref "R37") (pin "2") (pinfunction "2_2") (pintype "passive"))
      (node (ref "R38") (pin "1") (pinfunction "1_1") (pintype "passive"))
      (node (ref "S15") (pin "3") (pinfunction "3_3") (pintype "passive"))
    )
    (net (code "24") (name "Net-(D27-Pad1)") (class "Default")
      (node (ref "D27") (pin "1") (pinfunction "1_1") (pintype "passive"))
      (node (ref "R42") (pin "2") (pinfunction "2_2") (pintype "passive"))
      (node (ref "R43") (pin "1") (pinfunction "1_1") (pintype "passive"))
      (node (ref "S14") (pin "3") (pinfunction "3_3") (pintype "passive"))
    )
    (net (code "25") (name "Net-(D31-Pad1)") (class "Default")
      (node (ref "D31") (pin "1") (pinfunction "1_1") (pintype "passive"))
      (node (ref "R47") (pin "2") (pinfunction "2_2") (pintype "passive"))
      (node (ref "R48") (pin "1") (pinfunction "1_1") (pintype "passive"))
      (node (ref "S13") (pin "3") (pinfunction "3_3") (pintype "passive"))
    )
    (net (code "26") (name "Net-(D32-Pad1)") (class "Default")
      (node (ref "D32") (pin "1") (pinfunction "1_1") (pintype "passive"))
      (node (ref "R50") (pin "2") (pinfunction "2_2") (pintype "passive"))
      (node (ref "R52") (pin "1") (pinfunction "1_1") (pintype "passive"))
      (node (ref "S12") (pin "3") (pinfunction "3_3") (pintype "passive"))
    )
    (net (code "27") (name "Net-(J6-H)") (class "Default")
      (node (ref "D24") (pin "1") (pinfunction "1_1") (pintype "passive"))
      (node (ref "J6") (pin "H2") (pinfunction "H_H2") (pintype "passive"))
      (node (ref "R36") (pin "1") (pinfunction "1_1") (pintype "passive"))
    )
    (net (code "28") (name "Net-(J6-SEL+)") (class "Default")
      (node (ref "D25") (pin "1") (pinfunction "1_1") (pintype "passive"))
      (node (ref "J6") (pin "B1A") (pinfunction "SEL+_B1A") (pintype "passive"))
      (node (ref "R33") (pin "2") (pinfunction "2_2") (pintype "passive"))
      (node (ref "R35") (pin "1") (pinfunction "1_1") (pintype "passive"))
    )
    (net (code "29") (name "Net-(J6-V)") (class "Default")
      (node (ref "D23") (pin "1") (pinfunction "1_1") (pintype "passive"))
      (node (ref "J6") (pin "V2") (pinfunction "V_V2") (pintype "passive"))
      (node (ref "R39") (pin "1") (pinfunction "1_1") (pintype "passive"))
    )
    (net (code "30") (name "Net-(J7-H)") (class "Default")
      (node (ref "D29") (pin "1") (pinfunction "1_1") (pintype "passive"))
      (node (ref "J7") (pin "H2") (pinfunction "H_H2") (pintype "passive"))
      (node (ref "R45") (pin "1") (pinfunction "1_1") (pintype "passive"))
    )
    (net (code "31") (name "Net-(J7-SEL+)") (class "Default")
      (node (ref "D30") (pin "1") (pinfunction "1_1") (pintype "passive"))
      (node (ref "J7") (pin "B1A") (pinfunction "SEL+_B1A") (pintype "passive"))
      (node (ref "R41") (pin "2") (pinfunction "2_2") (pintype "passive"))
      (node (ref "R44") (pin "1") (pinfunction "1_1") (pintype "passive"))
    )
    (net (code "32") (name "Net-(J7-V)") (class "Default")
      (node (ref "D28") (pin "1") (pinfunction "1_1") (pintype "passive"))
      (node (ref "J7") (pin "V2") (pinfunction "V_V2") (pintype "passive"))
      (node (ref "R46") (pin "1") (pinfunction "1_1") (pintype "passive"))
    )
    (net (code "33") (name "Net-(J8-H)") (class "Default")
      (node (ref "D34") (pin "1") (pinfunction "1_1") (pintype "passive"))
      (node (ref "J8") (pin "H2") (pinfunction "H_H2") (pintype "passive"))
      (node (ref "R53") (pin "1") (pinfunction "1_1") (pintype "passive"))
    )
    (net (code "34") (name "Net-(J8-SEL+)") (class "Default")
      (node (ref "D35") (pin "1") (pinfunction "1_1") (pintype "passive"))
      (node (ref "J8") (pin "B1A") (pinfunction "SEL+_B1A") (pintype "passive"))
      (node (ref "R49") (pin "2") (pinfunction "2_2") (pintype "passive"))
      (node (ref "R51") (pin "1") (pinfunction "1_1") (pintype "passive"))
    )
    (net (code "35") (name "Net-(J8-V)") (class "Default")
      (node (ref "D33") (pin "1") (pinfunction "1_1") (pintype "passive"))
      (node (ref "J8") (pin "V2") (pinfunction "V_V2") (pintype "passive"))
      (node (ref "R54") (pin "1") (pinfunction "1_1") (pintype "passive"))
    )
    (net (code "36") (name "Net-(VR2-WIPER)") (class "Default")
      (node (ref "D26") (pin "1") (pinfunction "1_1") (pintype "passive"))
      (node (ref "R40") (pin "1") (pinfunction "1_1") (pintype "passive"))
      (node (ref "VR2") (pin "2") (pinfunction "WIPER_2") (pintype "passive"))
    )
    (net (code "37") (name "unconnected-(J6-SHIELD-PadS1)") (class "Default")
      (node (ref "J6") (pin "S1") (pinfunction "SHIELD_S1") (pintype "passive+no_connect"))
    )
    (net (code "38") (name "unconnected-(J6-SHIELD-PadS2)") (class "Default")
      (node (ref "J6") (pin "S2") (pinfunction "SHIELD_S2") (pintype "passive+no_connect"))
    )
    (net (code "39") (name "unconnected-(J6-SHIELD-PadS3)") (class "Default")
      (node (ref "J6") (pin "S3") (pinfunction "SHIELD_S3") (pintype "passive+no_connect"))
    )
    (net (code "40") (name "unconnected-(J6-SHIELD-PadS4)") (class "Default")
      (node (ref "J6") (pin "S4") (pinfunction "SHIELD_S4") (pintype "passive+no_connect"))
    )
    (net (code "41") (name "unconnected-(J7-SHIELD-PadS1)") (class "Default")
      (node (ref "J7") (pin "S1") (pinfunction "SHIELD_S1") (pintype "passive+no_connect"))
    )
    (net (code "42") (name "unconnected-(J7-SHIELD-PadS2)") (class "Default")
      (node (ref "J7") (pin "S2") (pinfunction "SHIELD_S2") (pintype "passive+no_connect"))
    )
    (net (code "43") (name "unconnected-(J7-SHIELD-PadS3)") (class "Default")
      (node (ref "J7") (pin "S3") (pinfunction "SHIELD_S3") (pintype "passive+no_connect"))
    )
    (net (code "44") (name "unconnected-(J7-SHIELD-PadS4)") (class "Default")
      (node (ref "J7") (pin "S4") (pinfunction "SHIELD_S4") (pintype "passive+no_connect"))
    )
    (net (code "45") (name "unconnected-(J8-SHIELD-PadS1)") (class "Default")
      (node (ref "J8") (pin "S1") (pinfunction "SHIELD_S1") (pintype "passive+no_connect"))
    )
    (net (code "46") (name "unconnected-(J8-SHIELD-PadS2)") (class "Default")
      (node (ref "J8") (pin "S2") (pinfunction "SHIELD_S2") (pintype "passive+no_connect"))
    )
    (net (code "47") (name "unconnected-(J8-SHIELD-PadS3)") (class "Default")
      (node (ref "J8") (pin "S3") (pinfunction "SHIELD_S3") (pintype "passive+no_connect"))
    )
    (net (code "48") (name "unconnected-(J8-SHIELD-PadS4)") (class "Default")
      (node (ref "J8") (pin "S4") (pinfunction "SHIELD_S4") (pintype "passive+no_connect"))
    )
    (net (code "49") (name "unconnected-(S12-Pad2)") (class "Default")
      (node (ref "S12") (pin "2") (pinfunction "2_2") (pintype "passive+no_connect"))
    )
    (net (code "50") (name "unconnected-(S12-Pad4)") (class "Default")
      (node (ref "S12") (pin "4") (pinfunction "4_4") (pintype "passive+no_connect"))
    )
    (net (code "51") (name "unconnected-(S13-Pad2)") (class "Default")
      (node (ref "S13") (pin "2") (pinfunction "2_2") (pintype "passive+no_connect"))
    )
    (net (code "52") (name "unconnected-(S13-Pad4)") (class "Default")
      (node (ref "S13") (pin "4") (pinfunction "4_4") (pintype "passive+no_connect"))
    )
    (net (code "53") (name "unconnected-(S14-Pad2)") (class "Default")
      (node (ref "S14") (pin "2") (pinfunction "2_2") (pintype "passive+no_connect"))
    )
    (net (code "54") (name "unconnected-(S14-Pad4)") (class "Default")
      (node (ref "S14") (pin "4") (pinfunction "4_4") (pintype "passive+no_connect"))
    )
    (net (code "55") (name "unconnected-(S15-Pad2)") (class "Default")
      (node (ref "S15") (pin "2") (pinfunction "2_2") (pintype "passive+no_connect"))
    )
    (net (code "56") (name "unconnected-(S15-Pad4)") (class "Default")
      (node (ref "S15") (pin "4") (pinfunction "4_4") (pintype "passive+no_connect"))
    )
    (net (code "57") (name "unconnected-(S16-Pad2)") (class "Default")
      (node (ref "S16") (pin "2") (pinfunction "2_2") (pintype "passive+no_connect"))
    )
    (net (code "58") (name "unconnected-(S16-Pad4)") (class "Default")
      (node (ref "S16") (pin "4") (pinfunction "4_4") (pintype "passive+no_connect"))
    )
    (net (code "59") (name "unconnected-(VR2-NC-Pad4)") (class "Default")
      (node (ref "VR2") (pin "4") (pinfunction "NC_4") (pintype "passive+no_connect"))
    )
    (net (code "60") (name "unconnected-(VR2-NC-Pad5)") (class "Default")
      (node (ref "VR2") (pin "5") (pinfunction "NC_5") (pintype "passive+no_connect"))
    )
    (net (code "61") (name "unconnected-(VR2-NC-Pad6)") (class "Default")
      (node (ref "VR2") (pin "6") (pinfunction "NC_6") (pintype "passive+no_connect"))
    )
    (net (code "62") (name "unconnected-(VR2-NC-Pad7)") (class "Default")
      (node (ref "VR2") (pin "7") (pinfunction "NC_7") (pintype "passive+no_connect"))
    )
  )
)
